# max7219_high_voltage.net
KiCad netlist of a schematic drawn in EAGLE
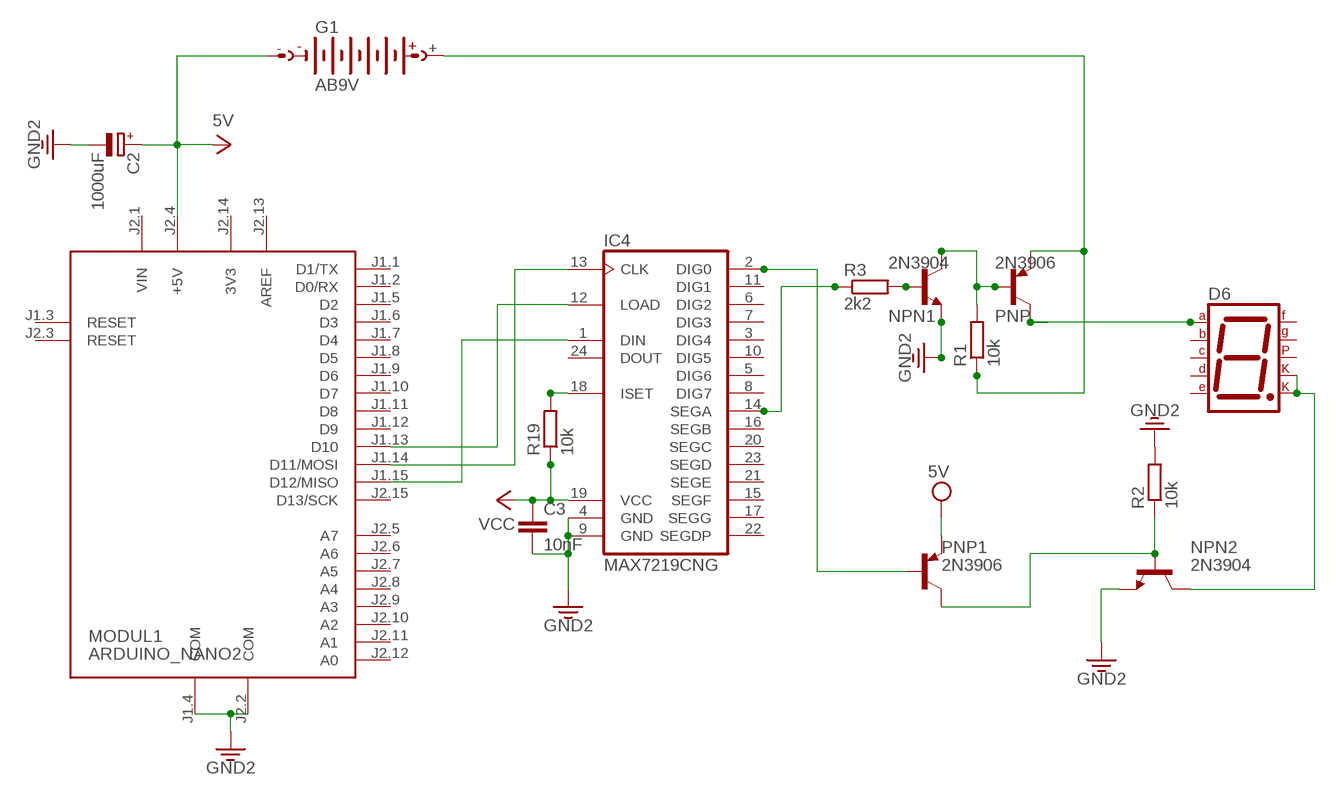
[diagram p0: schematic, sheet 1]

(export (version "E")
  (design (tool "Eeschema 10.0.6"))
  (components
    (comp (ref "C2")
      (value "1000uF")
      (footprint "eagle-import:E5-10,5")
      (libsource (lib "eagle-import") (part "CPOL-EUE5-10.5"))
    )
    (comp (ref "C3")
      (value "10nF")
      (footprint "eagle-import:C025-025X050")
      (libsource (lib "eagle-import") (part "C-EU025-025X050"))
    )
    (comp (ref "D6")
      (value "7SEG-MCK")
      (footprint "eagle-import:7SEG-7")
      (libsource (lib "eagle-import") (part "7SEG-MCK"))
    )
    (comp (ref "G1")
      (value "AB9V")
      (footprint "eagle-import:AB9V")
      (libsource (lib "eagle-import") (part "AB9V"))
    )
    (comp (ref "IC4")
      (value "MAX7219CNG")
      (footprint "eagle-import:DIL24-3")
      (fields (field (name "MF") "MAXIM"))
      (libsource (lib "eagle-import") (part "MAX7219CNG"))
    )
    (comp (ref "MODUL1")
      (value "ARDUINO_NANO2")
      (footprint "eagle-import:ARDUINO_NANO2")
      (libsource (lib "eagle-import") (part "ARDUINO_NANO2"))
    )
    (comp (ref "NPN1")
      (value "2N3904")
      (footprint "eagle-import:TO92")
      (libsource (lib "eagle-import") (part "2N3904"))
    )
    (comp (ref "NPN2")
      (value "2N3904")
      (footprint "eagle-import:TO92")
      (libsource (lib "eagle-import") (part "2N3904"))
    )
    (comp (ref "PNP")
      (value "2N3906")
      (footprint "eagle-import:TO92")
      (libsource (lib "eagle-import") (part "2N3906"))
    )
    (comp (ref "PNP1")
      (value "2N3906")
      (footprint "eagle-import:TO92")
      (libsource (lib "eagle-import") (part "2N3906"))
    )
    (comp (ref "R1")
      (value "10k")
      (footprint "eagle-import:0204_7")
      (libsource (lib "eagle-import") (part "R-EU_0204/7"))
    )
    (comp (ref "R2")
      (value "10k")
      (footprint "eagle-import:0204_7")
      (libsource (lib "eagle-import") (part "R-EU_0204/7"))
    )
    (comp (ref "R3")
      (value "2k2")
      (footprint "eagle-import:0204_7")
      (libsource (lib "eagle-import") (part "R-EU_0204/7"))
    )
    (comp (ref "R19")
      (value "10k")
      (footprint "eagle-import:0204_7")
      (libsource (lib "eagle-import") (part "R-EU_0204/7"))
    )
  )
  (nets
    (net (code "1") (name "/3V3") (class "Default")
      (node (ref "MODUL1") (pin "J2.14") (pinfunction "3V3_J2.14") (pintype "power_in"))
    )
    (net (code "2") (name "/AREF") (class "Default")
      (node (ref "MODUL1") (pin "J2.13") (pinfunction "AREF_J2.13") (pintype "power_in"))
    )
    (net (code "3") (name "/VIN") (class "Default")
      (node (ref "MODUL1") (pin "J2.1") (pinfunction "VIN_J2.1") (pintype "power_in"))
    )
    (net (code "4") (name "5V") (class "Default")
      (node (ref "C2") (pin "+") (pinfunction "+_+") (pintype "passive"))
      (node (ref "C3") (pin "1") (pinfunction "1_1") (pintype "passive"))
      (node (ref "G1") (pin "-") (pinfunction "-_-") (pintype "passive"))
      (node (ref "IC4") (pin "19") (pinfunction "VCC_19") (pintype "power_in"))
      (node (ref "MODUL1") (pin "J2.4") (pinfunction "+5V_J2.4") (pintype "power_in"))
      (node (ref "PNP1") (pin "3") (pinfunction "E_3") (pintype "passive"))
      (node (ref "R19") (pin "1") (pinfunction "1_1") (pintype "passive"))
    )
    (net (code "5") (name "GND2") (class "Default")
      (node (ref "C2") (pin "-") (pinfunction "-_-") (pintype "passive"))
      (node (ref "C3") (pin "2") (pinfunction "2_2") (pintype "passive"))
      (node (ref "IC4") (pin "4") (pinfunction "GND_4") (pintype "power_in"))
      (node (ref "IC4") (pin "9") (pinfunction "GND_9") (pintype "power_in"))
      (node (ref "MODUL1") (pin "J1.4") (pinfunction "COM_J1.4") (pintype "power_in"))
      (node (ref "MODUL1") (pin "J2.2") (pinfunction "COM_J2.2") (pintype "power_in"))
      (node (ref "NPN1") (pin "3") (pinfunction "E_3") (pintype "passive"))
      (node (ref "NPN2") (pin "3") (pinfunction "E_3") (pintype "passive"))
      (node (ref "R2") (pin "2") (pinfunction "2_2") (pintype "passive"))
    )
    (net (code "6") (name "Net-(D6-A)") (class "Default")
      (node (ref "D6") (pin "10") (pinfunction "A_10") (pintype "passive"))
      (node (ref "PNP") (pin "1") (pinfunction "C_1") (pintype "passive"))
    )
    (net (code "7") (name "Net-(D6-CK1)") (class "Default")
      (node (ref "D6") (pin "1") (pinfunction "CK1_1") (pintype "passive"))
      (node (ref "D6") (pin "6") (pinfunction "CK2_6") (pintype "passive"))
      (node (ref "NPN2") (pin "1") (pinfunction "C_1") (pintype "passive"))
    )
    (net (code "8") (name "Net-(IC4-CLK)") (class "Default")
      (node (ref "IC4") (pin "13") (pinfunction "CLK_13") (pintype "input"))
      (node (ref "MODUL1") (pin "J1.14") (pinfunction "D11/MOSI_J1.14") (pintype "bidirectional"))
    )
    (net (code "9") (name "Net-(IC4-DIG0)") (class "Default")
      (node (ref "IC4") (pin "2") (pinfunction "DIG0_2") (pintype "output"))
      (node (ref "PNP1") (pin "2") (pinfunction "B_2") (pintype "passive"))
    )
    (net (code "10") (name "Net-(IC4-DIN)") (class "Default")
      (node (ref "IC4") (pin "1") (pinfunction "DIN_1") (pintype "input"))
      (node (ref "MODUL1") (pin "J1.15") (pinfunction "D12/MISO_J1.15") (pintype "bidirectional"))
    )
    (net (code "11") (name "Net-(IC4-ISET)") (class "Default")
      (node (ref "IC4") (pin "18") (pinfunction "ISET_18") (pintype "input"))
      (node (ref "R19") (pin "2") (pinfunction "2_2") (pintype "passive"))
    )
    (net (code "12") (name "Net-(IC4-LOAD)") (class "Default")
      (node (ref "IC4") (pin "12") (pinfunction "LOAD_12") (pintype "input"))
      (node (ref "MODUL1") (pin "J1.13") (pinfunction "D10_J1.13") (pintype "bidirectional"))
    )
    (net (code "13") (name "Net-(IC4-SEGA)") (class "Default")
      (node (ref "IC4") (pin "14") (pinfunction "SEGA_14") (pintype "output"))
      (node (ref "R3") (pin "1") (pinfunction "1_1") (pintype "passive"))
    )
    (net (code "14") (name "Net-(NPN1-B)") (class "Default")
      (node (ref "NPN1") (pin "2") (pinfunction "B_2") (pintype "passive"))
      (node (ref "R3") (pin "2") (pinfunction "2_2") (pintype "passive"))
    )
    (net (code "15") (name "Net-(NPN1-C)") (class "Default")
      (node (ref "NPN1") (pin "1") (pinfunction "C_1") (pintype "passive"))
      (node (ref "PNP") (pin "2") (pinfunction "B_2") (pintype "passive"))
      (node (ref "R1") (pin "2") (pinfunction "2_2") (pintype "passive"))
    )
    (net (code "16") (name "Net-(NPN2-B)") (class "Default")
      (node (ref "NPN2") (pin "2") (pinfunction "B_2") (pintype "passive"))
      (node (ref "PNP1") (pin "1") (pinfunction "C_1") (pintype "passive"))
      (node (ref "R2") (pin "1") (pinfunction "1_1") (pintype "passive"))
    )
    (net (code "17") (name "Net-(PNP-E)") (class "Default")
      (node (ref "G1") (pin "+") (pinfunction "+_+") (pintype "passive"))
      (node (ref "PNP") (pin "3") (pinfunction "E_3") (pintype "passive"))
      (node (ref "R1") (pin "1") (pinfunction "1_1") (pintype "passive"))
    )
    (net (code "18") (name "unconnected-(D6-B-Pad9)") (class "Default")
      (node (ref "D6") (pin "9") (pinfunction "B_9") (pintype "passive"))
    )
    (net (code "19") (name "unconnected-(D6-C-Pad8)") (class "Default")
      (node (ref "D6") (pin "8") (pinfunction "C_8") (pintype "passive"))
    )
    (net (code "20") (name "unconnected-(D6-D-Pad5)") (class "Default")
      (node (ref "D6") (pin "5") (pinfunction "D_5") (pintype "passive"))
    )
    (net (code "21") (name "unconnected-(D6-DP-Pad7)") (class "Default")
      (node (ref "D6") (pin "7") (pinfunction "DP_7") (pintype "passive"))
    )
    (net (code "22") (name "unconnected-(D6-E-Pad4)") (class "Default")
      (node (ref "D6") (pin "4") (pinfunction "E_4") (pintype "passive"))
    )
    (net (code "23") (name "unconnected-(D6-F-Pad2)") (class "Default")
      (node (ref "D6") (pin "2") (pinfunction "F_2") (pintype "passive"))
    )
    (net (code "24") (name "unconnected-(D6-G-Pad3)") (class "Default")
      (node (ref "D6") (pin "3") (pinfunction "G_3") (pintype "passive"))
    )
    (net (code "25") (name "unconnected-(IC4-DIG1-Pad11)") (class "Default")
      (node (ref "IC4") (pin "11") (pinfunction "DIG1_11") (pintype "output"))
    )
    (net (code "26") (name "unconnected-(IC4-DIG2-Pad6)") (class "Default")
      (node (ref "IC4") (pin "6") (pinfunction "DIG2_6") (pintype "output"))
    )
    (net (code "27") (name "unconnected-(IC4-DIG3-Pad7)") (class "Default")
      (node (ref "IC4") (pin "7") (pinfunction "DIG3_7") (pintype "output"))
    )
    (net (code "28") (name "unconnected-(IC4-DIG4-Pad3)") (class "Default")
      (node (ref "IC4") (pin "3") (pinfunction "DIG4_3") (pintype "output"))
    )
    (net (code "29") (name "unconnected-(IC4-DIG5-Pad10)") (class "Default")
      (node (ref "IC4") (pin "10") (pinfunction "DIG5_10") (pintype "output"))
    )
    (net (code "30") (name "unconnected-(IC4-DIG6-Pad5)") (class "Default")
      (node (ref "IC4") (pin "5") (pinfunction "DIG6_5") (pintype "output"))
    )
    (net (code "31") (name "unconnected-(IC4-DIG7-Pad8)") (class "Default")
      (node (ref "IC4") (pin "8") (pinfunction "DIG7_8") (pintype "output"))
    )
    (net (code "32") (name "unconnected-(IC4-DOUT-Pad24)") (class "Default")
      (node (ref "IC4") (pin "24") (pinfunction "DOUT_24") (pintype "output"))
    )
    (net (code "33") (name "unconnected-(IC4-SEGB-Pad16)") (class "Default")
      (node (ref "IC4") (pin "16") (pinfunction "SEGB_16") (pintype "output"))
    )
    (net (code "34") (name "unconnected-(IC4-SEGC-Pad20)") (class "Default")
      (node (ref "IC4") (pin "20") (pinfunction "SEGC_20") (pintype "output"))
    )
    (net (code "35") (name "unconnected-(IC4-SEGD-Pad23)") (class "Default")
      (node (ref "IC4") (pin "23") (pinfunction "SEGD_23") (pintype "output"))
    )
    (net (code "36") (name "unconnected-(IC4-SEGDP-Pad22)") (class "Default")
      (node (ref "IC4") (pin "22") (pinfunction "SEGDP_22") (pintype "output"))
    )
    (net (code "37") (name "unconnected-(IC4-SEGE-Pad21)") (class "Default")
      (node (ref "IC4") (pin "21") (pinfunction "SEGE_21") (pintype "output"))
    )
    (net (code "38") (name "unconnected-(IC4-SEGF-Pad15)") (class "Default")
      (node (ref "IC4") (pin "15") (pinfunction "SEGF_15") (pintype "output"))
    )
    (net (code "39") (name "unconnected-(IC4-SEGG-Pad17)") (class "Default")
      (node (ref "IC4") (pin "17") (pinfunction "SEGG_17") (pintype "output"))
    )
    (net (code "40") (name "unconnected-(MODUL1-A0-PadJ2.12)") (class "Default")
      (node (ref "MODUL1") (pin "J2.12") (pinfunction "A0_J2.12") (pintype "bidirectional"))
    )
    (net (code "41") (name "unconnected-(MODUL1-A1-PadJ2.11)") (class "Default")
      (node (ref "MODUL1") (pin "J2.11") (pinfunction "A1_J2.11") (pintype "bidirectional"))
    )
    (net (code "42") (name "unconnected-(MODUL1-A2-PadJ2.10)") (class "Default")
      (node (ref "MODUL1") (pin "J2.10") (pinfunction "A2_J2.10") (pintype "bidirectional"))
    )
    (net (code "43") (name "unconnected-(MODUL1-A3-PadJ2.9)") (class "Default")
      (node (ref "MODUL1") (pin "J2.9") (pinfunction "A3_J2.9") (pintype "bidirectional"))
    )
    (net (code "44") (name "unconnected-(MODUL1-A4-PadJ2.8)") (class "Default")
      (node (ref "MODUL1") (pin "J2.8") (pinfunction "A4_J2.8") (pintype "bidirectional"))
    )
    (net (code "45") (name "unconnected-(MODUL1-A5-PadJ2.7)") (class "Default")
      (node (ref "MODUL1") (pin "J2.7") (pinfunction "A5_J2.7") (pintype "bidirectional"))
    )
    (net (code "46") (name "unconnected-(MODUL1-A6-PadJ2.6)") (class "Default")
      (node (ref "MODUL1") (pin "J2.6") (pinfunction "A6_J2.6") (pintype "bidirectional"))
    )
    (net (code "47") (name "unconnected-(MODUL1-A7-PadJ2.5)") (class "Default")
      (node (ref "MODUL1") (pin "J2.5") (pinfunction "A7_J2.5") (pintype "bidirectional"))
    )
    (net (code "48") (name "unconnected-(MODUL1-D0{slash}RX-PadJ1.2)") (class "Default")
      (node (ref "MODUL1") (pin "J1.2") (pinfunction "D0/RX_J1.2") (pintype "bidirectional"))
    )
    (net (code "49") (name "unconnected-(MODUL1-D1{slash}TX-PadJ1.1)") (class "Default")
      (node (ref "MODUL1") (pin "J1.1") (pinfunction "D1/TX_J1.1") (pintype "bidirectional"))
    )
    (net (code "50") (name "unconnected-(MODUL1-D2-PadJ1.5)") (class "Default")
      (node (ref "MODUL1") (pin "J1.5") (pinfunction "D2_J1.5") (pintype "bidirectional"))
    )
    (net (code "51") (name "unconnected-(MODUL1-D3-PadJ1.6)") (class "Default")
      (node (ref "MODUL1") (pin "J1.6") (pinfunction "D3_J1.6") (pintype "bidirectional"))
    )
    (net (code "52") (name "unconnected-(MODUL1-D4-PadJ1.7)") (class "Default")
      (node (ref "MODUL1") (pin "J1.7") (pinfunction "D4_J1.7") (pintype "bidirectional"))
    )
    (net (code "53") (name "unconnected-(MODUL1-D5-PadJ1.8)") (class "Default")
      (node (ref "MODUL1") (pin "J1.8") (pinfunction "D5_J1.8") (pintype "bidirectional"))
    )
    (net (code "54") (name "unconnected-(MODUL1-D6-PadJ1.9)") (class "Default")
      (node (ref "MODUL1") (pin "J1.9") (pinfunction "D6_J1.9") (pintype "bidirectional"))
    )
    (net (code "55") (name "unconnected-(MODUL1-D7-PadJ1.10)") (class "Default")
      (node (ref "MODUL1") (pin "J1.10") (pinfunction "D7_J1.10") (pintype "bidirectional"))
    )
    (net (code "56") (name "unconnected-(MODUL1-D8-PadJ1.11)") (class "Default")
      (node (ref "MODUL1") (pin "J1.11") (pinfunction "D8_J1.11") (pintype "bidirectional"))
    )
    (net (code "57") (name "unconnected-(MODUL1-D9-PadJ1.12)") (class "Default")
      (node (ref "MODUL1") (pin "J1.12") (pinfunction "D9_J1.12") (pintype "bidirectional"))
    )
    (net (code "58") (name "unconnected-(MODUL1-D13{slash}SCK-PadJ2.15)") (class "Default")
      (node (ref "MODUL1") (pin "J2.15") (pinfunction "D13/SCK_J2.15") (pintype "bidirectional"))
    )
    (net (code "59") (name "unconnected-(MODUL1-RESET-PadJ1.3)") (class "Default")
      (node (ref "MODUL1") (pin "J1.3") (pinfunction "RESET_J1.3") (pintype "bidirectional"))
    )
    (net (code "60") (name "unconnected-(MODUL1-RESET-PadJ2.3)") (class "Default")
      (node (ref "MODUL1") (pin "J2.3") (pinfunction "RESET_J2.3") (pintype "bidirectional"))
    )
  )
)
